# sha2017_rev1_0_0_1.net
KiCad netlist of a schematic drawn in Altium Designer
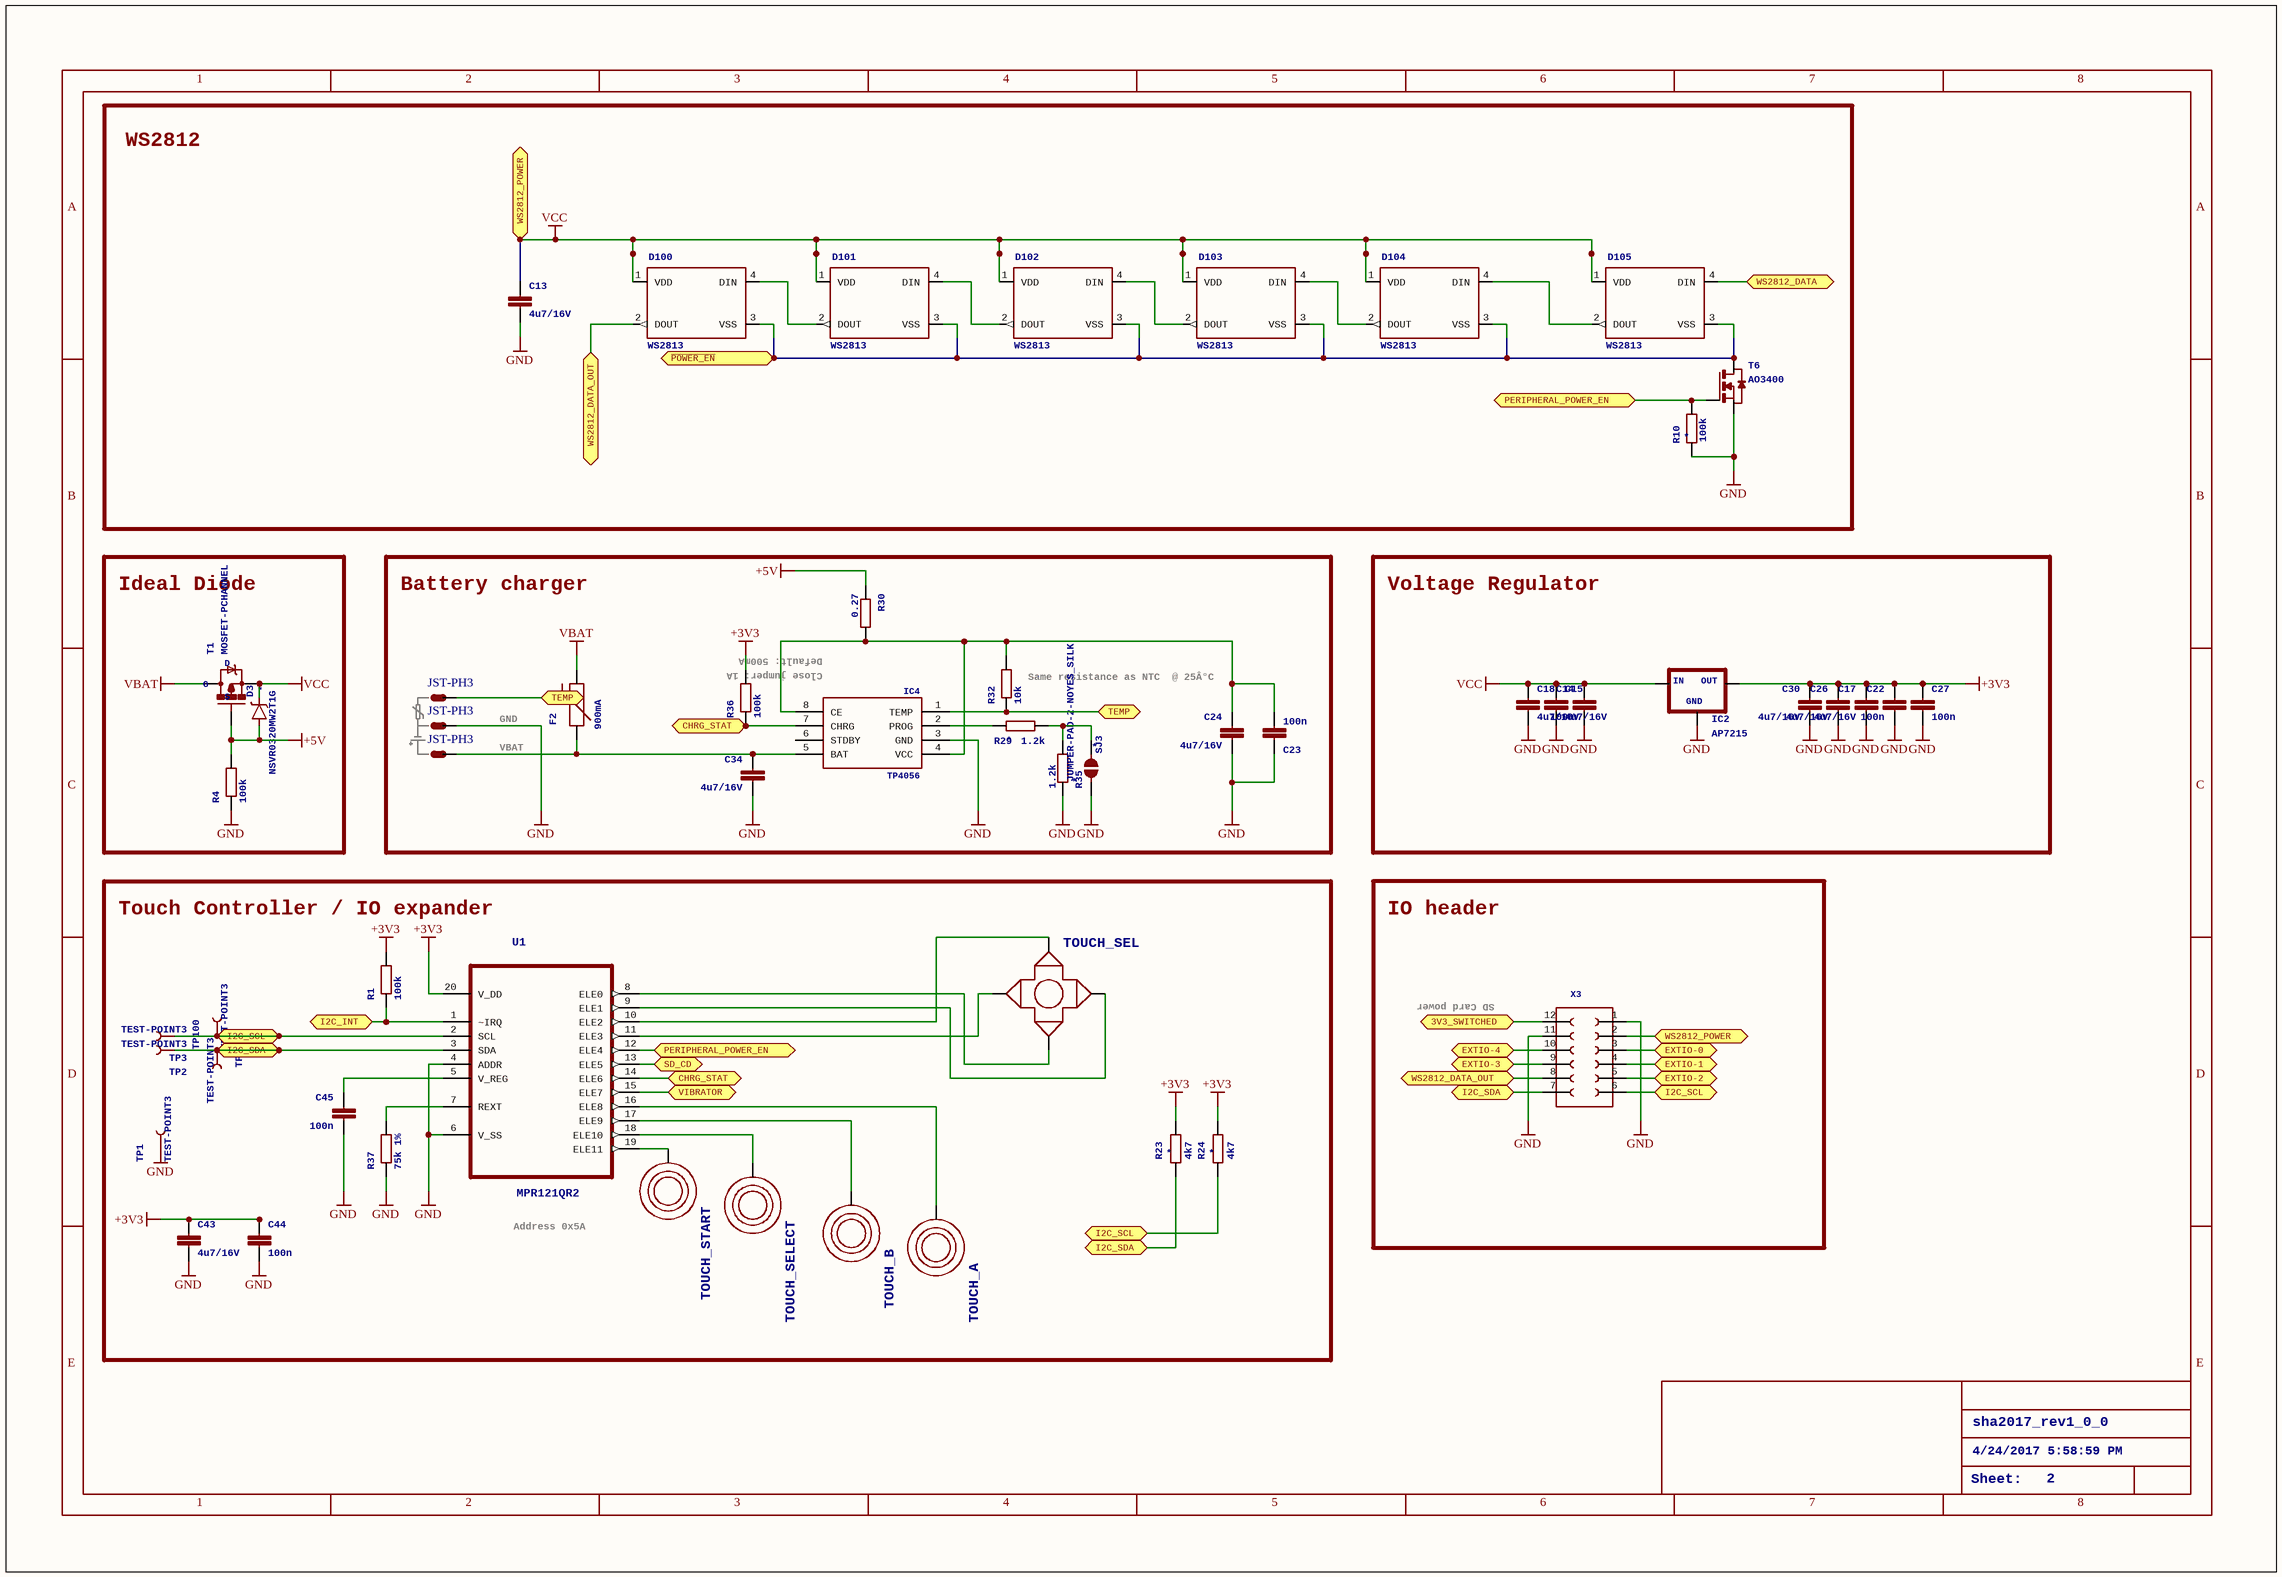
[diagram p0: sha2017_rev1_0_0_1.SchDoc]

(export (version "E")
  (design (tool "Eeschema 10.0.6"))
  (components
    (comp (ref "C13")
      (value "4u7/16V")
      (footprint "C0805")
      (description "CAPACITOR, European symbol")
      (libsource (lib "") (part "C-EUC0805_1"))
    )
    (comp (ref "C14") (value "100n") (footprint "C0603-DASHES") (libsource (lib "") (part "C0603-DASHES_1")))
    (comp (ref "C15")
      (value "4u7/16V")
      (footprint "C0805")
      (description "CAPACITOR, European symbol")
      (libsource (lib "") (part "C-EUC0805_1"))
    )
    (comp (ref "C17")
      (value "4u7/16V")
      (footprint "C0805")
      (description "CAPACITOR, European symbol")
      (libsource (lib "rcl") (part "C-EUC0805"))
    )
    (comp (ref "C18")
      (value "4u7/16V")
      (footprint "C0805")
      (description "CAPACITOR, European symbol")
      (libsource (lib "") (part "C-EUC0805_1"))
    )
    (comp (ref "C22") (value "100n") (footprint "C0603-DASHES") (libsource (lib "") (part "C0603-DASHES_1")))
    (comp (ref "C23")
      (value "100n")
      (footprint "C0603-DASHES")
      (libsource (lib "sha2017_rev0_1_0_dev") (part "C0603-DASHES"))
    )
    (comp (ref "C24")
      (value "4u7/16V")
      (footprint "C0805")
      (description "CAPACITOR, European symbol")
      (libsource (lib "rcl") (part "C-EUC0805"))
    )
    (comp (ref "C26")
      (value "4u7/16V")
      (footprint "C0805")
      (description "CAPACITOR, European symbol")
      (libsource (lib "rcl") (part "C-EUC0805"))
    )
    (comp (ref "C27") (value "100n") (footprint "C0603-DASHES") (libsource (lib "") (part "C0603-DASHES_2")))
    (comp (ref "C30")
      (value "4u7/16V")
      (footprint "C0805")
      (description "CAPACITOR, European symbol")
      (libsource (lib "rcl") (part "C-EUC0805"))
    )
    (comp (ref "C34")
      (value "4u7/16V")
      (footprint "C0805")
      (description "CAPACITOR, European symbol")
      (libsource (lib "rcl") (part "C-EUC0805"))
    )
    (comp (ref "C43")
      (value "4u7/16V")
      (footprint "C0805")
      (description "CAPACITOR, European symbol")
      (libsource (lib "") (part "C-EUC0805_1"))
    )
    (comp (ref "C44") (value "100n") (footprint "C0603-DASHES") (libsource (lib "") (part "C0603-DASHES_2")))
    (comp (ref "C45") (value "100n") (footprint "C0603-DASHES") (libsource (lib "") (part "C0603-DASHES_1")))
    (comp (ref "D3")
      (value "NSVR0320MW2T1G")
      (footprint "SOD-323")
      (description "23V, 1A Schottky diode, SOD-323 package")
      (fields (field (name "NAME") "*"))
      (libsource (lib "SparkFun-DiscreteSemi") (part "BAT20JFILM"))
    )
    (comp (ref "D100")
      (value "WS2813")
      (footprint "WS2812B")
      (libsource (lib "SparkFun-LED") (part "WS2812B"))
    )
    (comp (ref "D101")
      (value "WS2813")
      (footprint "WS2812B")
      (libsource (lib "SparkFun-LED") (part "WS2812B"))
    )
    (comp (ref "D102")
      (value "WS2813")
      (footprint "WS2812B")
      (libsource (lib "SparkFun-LED") (part "WS2812B"))
    )
    (comp (ref "D103")
      (value "WS2813")
      (footprint "WS2812B")
      (libsource (lib "SparkFun-LED") (part "WS2812B"))
    )
    (comp (ref "D104")
      (value "WS2813")
      (footprint "WS2812B")
      (libsource (lib "SparkFun-LED") (part "WS2812B"))
    )
    (comp (ref "D105")
      (value "WS2813")
      (footprint "WS2812B")
      (libsource (lib "SparkFun-LED") (part "WS2812B"))
    )
    (comp (ref "F2")
      (value "900mA")
      (footprint "PTC-1206")
      (description "Resettable Fuse PTCResettable Fuse. Spark Fun Electronics SKU : COM-08357")
      (libsource (lib "SparkFun-PowerIC") (part "PTCSMD"))
    )
    (comp (ref "IC2")
      (value "AP7215")
      (footprint "SOT89")
      (fields (field (name "GND") "GND") (field (name "IN") "IN") (field (name "OUT") "OUT"))
      (libsource (lib "badge") (part "AP7215"))
    )
    (comp (ref "IC4") (value "TP4056") (footprint "SOP-8") (libsource (lib "TP4056") (part "TP4056")))
    (comp (ref "R1")
      (value "100k")
      (footprint "R0603-DASHES")
      (libsource (lib "sha2017_rev0_1_0_dev") (part "R0603-DASHES"))
    )
    (comp (ref "R4")
      (value "100k")
      (footprint "R0603-DASHES")
      (libsource (lib "sha2017_rev0_1_0_dev") (part "R0603-DASHES"))
    )
    (comp (ref "R10")
      (value "100k")
      (footprint "R0603-DASHES")
      (fields (field (name "NAME") "*"))
      (libsource (lib "00ralf") (part "R0603-DASHES"))
    )
    (comp (ref "R23")
      (value "4k7")
      (footprint "R0603-DASHES")
      (fields (field (name "NAME") "*"))
      (libsource (lib "sha2017_rev0_1_0_dev") (part "R0603-DASHES"))
    )
    (comp (ref "R24")
      (value "4k7")
      (footprint "R0603-DASHES")
      (fields (field (name "NAME") "*"))
      (libsource (lib "sha2017_rev0_1_0_dev") (part "R0603-DASHES"))
    )
    (comp (ref "R29")
      (value "1.2k")
      (footprint "R0603-DASHES")
      (fields (field (name "NAME") "*"))
      (libsource (lib "sha2017_rev0_1_0_dev") (part "R0603-DASHES"))
    )
    (comp (ref "R30")
      (value "0.27")
      (footprint "R0603-DASHES")
      (libsource (lib "sha2017_rev0_1_0_dev") (part "R0603-DASHES"))
    )
    (comp (ref "R32")
      (value "10k")
      (footprint "R0603-DASHES")
      (libsource (lib "sha2017_rev0_1_0_dev") (part "R0603-DASHES"))
    )
    (comp (ref "R35")
      (value "1.2k")
      (footprint "R0603-DASHES")
      (fields (field (name "NAME") "*"))
      (libsource (lib "sha2017_rev0_1_0_dev") (part "R0603-DASHES"))
    )
    (comp (ref "R36")
      (value "100k")
      (footprint "R0603-DASHES")
      (libsource (lib "sha2017_rev0_1_0_dev") (part "R0603-DASHES"))
    )
    (comp (ref "R37")
      (value "75k 1%")
      (footprint "R0603-DASHES")
      (libsource (lib "sha2017_rev0_1_0_dev") (part "R0603-DASHES"))
    )
    (comp (ref "SJ3")
      (value "JUMPER-PAD-2-NOYES_SILK")
      (footprint "PAD-JUMPER-2-NO_YES_SILK")
      (fields (field (name "NAME") "*"))
      (libsource (lib "SparkFun-Passives") (part "JUMPER-PAD-2-NOYES_SILK"))
    )
    (comp (ref "T1")
      (value "MOSFET-PCHANNEL")
      (footprint "SOT23-3")
      (fields (field (name "D") "D") (field (name "S") "S") (field (name "G") "G"))
      (libsource (lib "SparkFun-DiscreteSemi") (part "MOSFET-PCHANNEL"))
    )
    (comp (ref "T6")
      (value "AO3400")
      (footprint "SOT-23")
      (description "MOS FET")
      (libsource (lib "zetex") (part "NMOSSOT23"))
    )
    (comp (ref "TOUCH_A")
      (value "TOUCHROUND")
      (footprint "TOUCH_BUTTON")
      (libsource (lib "badge") (part "TOUCHROUND"))
    )
    (comp (ref "TOUCH_B")
      (value "TOUCHROUND")
      (footprint "TOUCH_BUTTON")
      (libsource (lib "badge") (part "TOUCHROUND"))
    )
    (comp (ref "TOUCH_SEL")
      (value "TOUCH_CROSS")
      (footprint "TOUCH_CROSS")
      (libsource (lib "badge") (part "TOUCH_CROSS"))
    )
    (comp (ref "TOUCH_SELECT")
      (value "TOUCHSELECT")
      (footprint "TOUCH_SELECT")
      (libsource (lib "badge") (part "TOUCHSELECT"))
    )
    (comp (ref "TOUCH_START")
      (value "TOUCHSELECT")
      (footprint "TOUCH_SELECT")
      (libsource (lib "badge") (part "TOUCHSELECT"))
    )
    (comp (ref "TP1")
      (value "TEST-POINT3")
      (footprint "PAD.03X.03")
      (description "Bare copper test points for troubleshooting or ICT")
      (libsource (lib "SparkFun-Passives") (part "TEST-POINT3"))
    )
    (comp (ref "TP2")
      (value "TEST-POINT3")
      (footprint "PAD.03X.03")
      (description "Bare copper test points for troubleshooting or ICT")
      (libsource (lib "SparkFun-Passives") (part "TEST-POINT3"))
    )
    (comp (ref "TP3")
      (value "TEST-POINT3")
      (footprint "PAD.03X.03")
      (description "Bare copper test points for troubleshooting or ICT")
      (libsource (lib "SparkFun-Passives") (part "TEST-POINT3"))
    )
    (comp (ref "TP100")
      (value "TEST-POINT3")
      (footprint "PAD.03X.03")
      (description "Bare copper test points for troubleshooting or ICT")
      (libsource (lib "SparkFun-Passives") (part "TEST-POINT3"))
    )
    (comp (ref "TP101")
      (value "TEST-POINT3")
      (footprint "PAD.03X.03")
      (description "Bare copper test points for troubleshooting or ICT")
      (libsource (lib "SparkFun-Passives") (part "TEST-POINT3"))
    )
    (comp (ref "U1")
      (value "MPR121QR2")
      (footprint "QFN40P300X300X60-20N")
      (description "Proximity Capacitive Touch Sensor Controller")
      (libsource (lib "Freescale_By_element14_Batch_1") (part "MPR121QR2"))
    )
    (comp (ref "X3")
      (value "610X12243021")
      (footprint "610X12243021")
      (libsource (lib "EAGLE-BOARD-TO-BOARD_CONNECTORS-rev16c") (part "610X12243021"))
    )
    (comp (ref "X4") (value "JST-PH3") (footprint "JST-PH3") (libsource (lib "badge") (part "JST-PH3")))
  )
  (nets
    (net (code "1") (name "+3V3") (class "Default")
      (node (ref "C17") (pin "1") (pinfunction "1_1") (pintype "passive"))
      (node (ref "C22") (pin "1") (pinfunction "1_1") (pintype "passive"))
      (node (ref "C26") (pin "1") (pinfunction "1_1") (pintype "passive"))
      (node (ref "C27") (pin "1") (pinfunction "1_1") (pintype "passive"))
      (node (ref "C30") (pin "1") (pinfunction "1_1") (pintype "passive"))
      (node (ref "C43") (pin "1") (pinfunction "1_1") (pintype "passive"))
      (node (ref "C44") (pin "1") (pinfunction "1_1") (pintype "passive"))
      (node (ref "IC2") (pin "3") (pinfunction "OUT_3") (pintype "passive"))
      (node (ref "R1") (pin "2") (pinfunction "2_2") (pintype "passive"))
      (node (ref "R23") (pin "1") (pinfunction "1_1") (pintype "passive"))
      (node (ref "R24") (pin "1") (pinfunction "1_1") (pintype "passive"))
      (node (ref "R36") (pin "2") (pinfunction "2_2") (pintype "passive"))
      (node (ref "U1") (pin "20") (pinfunction "V_DD_20") (pintype "power_in"))
    )
    (net (code "2") (name "+5V") (class "Default")
      (node (ref "D3") (pin "A") (pinfunction "A_A") (pintype "passive"))
      (node (ref "R30") (pin "1") (pinfunction "1_1") (pintype "passive"))
      (node (ref "R4") (pin "2") (pinfunction "2_2") (pintype "passive"))
      (node (ref "T1") (pin "1") (pinfunction "G_1") (pintype "passive"))
    )
    (net (code "3") (name "/3V3_SWITCHED") (class "Default")
      (node (ref "X3") (pin "12") (pinfunction "1_12") (pintype "passive"))
    )
    (net (code "4") (name "/CHRG_STAT") (class "Default")
      (node (ref "IC4") (pin "7") (pinfunction "CHRG_7") (pintype "passive"))
      (node (ref "R36") (pin "1") (pinfunction "1_1") (pintype "passive"))
      (node (ref "U1") (pin "14") (pinfunction "ELE6_14") (pintype "output"))
    )
    (net (code "5") (name "/EXTIO-0") (class "Default")
      (node (ref "X3") (pin "3") (pinfunction "10_3") (pintype "passive"))
    )
    (net (code "6") (name "/EXTIO-1") (class "Default")
      (node (ref "X3") (pin "4") (pinfunction "9_4") (pintype "passive"))
    )
    (net (code "7") (name "/EXTIO-2") (class "Default")
      (node (ref "X3") (pin "5") (pinfunction "8_5") (pintype "passive"))
    )
    (net (code "8") (name "/EXTIO-3") (class "Default")
      (node (ref "X3") (pin "9") (pinfunction "4_9") (pintype "passive"))
    )
    (net (code "9") (name "/EXTIO-4") (class "Default")
      (node (ref "X3") (pin "10") (pinfunction "3_10") (pintype "passive"))
    )
    (net (code "10") (name "/I2C_INT") (class "Default")
      (node (ref "R1") (pin "1") (pinfunction "1_1") (pintype "passive"))
      (node (ref "U1") (pin "1") (pinfunction "~IRQ_1") (pintype "passive"))
    )
    (net (code "11") (name "/I2C_SCL") (class "Default")
      (node (ref "R24") (pin "2") (pinfunction "2_2") (pintype "passive"))
      (node (ref "TP100") (pin "P$1") (pinfunction "1_P$1") (pintype "passive"))
      (node (ref "TP3") (pin "P$1") (pinfunction "1_P$1") (pintype "passive"))
      (node (ref "U1") (pin "2") (pinfunction "SCL_2") (pintype "passive"))
      (node (ref "X3") (pin "6") (pinfunction "7_6") (pintype "passive"))
    )
    (net (code "12") (name "/I2C_SDA") (class "Default")
      (node (ref "R23") (pin "2") (pinfunction "2_2") (pintype "passive"))
      (node (ref "TP101") (pin "P$1") (pinfunction "1_P$1") (pintype "passive"))
      (node (ref "TP2") (pin "P$1") (pinfunction "1_P$1") (pintype "passive"))
      (node (ref "U1") (pin "3") (pinfunction "SDA_3") (pintype "passive"))
      (node (ref "X3") (pin "7") (pinfunction "6_7") (pintype "passive"))
    )
    (net (code "13") (name "/PERIPHERAL_POWER_EN") (class "Default")
      (node (ref "R10") (pin "1") (pinfunction "1_1") (pintype "passive"))
      (node (ref "T6") (pin "3") (pinfunction "G_3") (pintype "passive"))
      (node (ref "U1") (pin "12") (pinfunction "ELE4_12") (pintype "output"))
    )
    (net (code "14") (name "/SD_CD") (class "Default")
      (node (ref "U1") (pin "13") (pinfunction "ELE5_13") (pintype "output"))
    )
    (net (code "15") (name "/TEMP") (class "Default")
      (node (ref "IC4") (pin "1") (pinfunction "TEMP_1") (pintype "passive"))
      (node (ref "R32") (pin "1") (pinfunction "1_1") (pintype "passive"))
      (node (ref "X4") (pin "1") (pinfunction "1_1") (pintype "passive"))
    )
    (net (code "16") (name "/VIBRATOR") (class "Default")
      (node (ref "U1") (pin "15") (pinfunction "ELE7_15") (pintype "output"))
    )
    (net (code "17") (name "/WS2812_DATA") (class "Default")
      (node (ref "D105") (pin "4") (pinfunction "DIN_4") (pintype "passive"))
    )
    (net (code "18") (name "/WS2812_DATA_OUT") (class "Default")
      (node (ref "D100") (pin "2") (pinfunction "DOUT_2") (pintype "output"))
      (node (ref "X3") (pin "8") (pinfunction "5_8") (pintype "passive"))
    )
    (net (code "19") (name "/~{POWER_EN}") (class "Default")
      (node (ref "D100") (pin "3") (pinfunction "VSS_3") (pintype "power_in"))
      (node (ref "D101") (pin "3") (pinfunction "VSS_3") (pintype "power_in"))
      (node (ref "D102") (pin "3") (pinfunction "VSS_3") (pintype "power_in"))
      (node (ref "D103") (pin "3") (pinfunction "VSS_3") (pintype "power_in"))
      (node (ref "D104") (pin "3") (pinfunction "VSS_3") (pintype "power_in"))
      (node (ref "D105") (pin "3") (pinfunction "VSS_3") (pintype "power_in"))
      (node (ref "T6") (pin "1") (pinfunction "D_1") (pintype "passive"))
    )
    (net (code "20") (name "GND") (class "Default")
      (node (ref "C13") (pin "2") (pinfunction "2_2") (pintype "passive"))
      (node (ref "C14") (pin "2") (pinfunction "2_2") (pintype "passive"))
      (node (ref "C15") (pin "2") (pinfunction "2_2") (pintype "passive"))
      (node (ref "C17") (pin "2") (pinfunction "2_2") (pintype "passive"))
      (node (ref "C18") (pin "2") (pinfunction "2_2") (pintype "passive"))
      (node (ref "C22") (pin "2") (pinfunction "2_2") (pintype "passive"))
      (node (ref "C23") (pin "1") (pinfunction "1_1") (pintype "passive"))
      (node (ref "C24") (pin "2") (pinfunction "2_2") (pintype "passive"))
      (node (ref "C26") (pin "2") (pinfunction "2_2") (pintype "passive"))
      (node (ref "C27") (pin "2") (pinfunction "2_2") (pintype "passive"))
      (node (ref "C30") (pin "2") (pinfunction "2_2") (pintype "passive"))
      (node (ref "C34") (pin "2") (pinfunction "2_2") (pintype "passive"))
      (node (ref "C43") (pin "2") (pinfunction "2_2") (pintype "passive"))
      (node (ref "C44") (pin "2") (pinfunction "2_2") (pintype "passive"))
      (node (ref "C45") (pin "2") (pinfunction "2_2") (pintype "passive"))
      (node (ref "IC2") (pin "1") (pinfunction "GND_1") (pintype "passive"))
      (node (ref "IC4") (pin "3") (pinfunction "GND_3") (pintype "passive"))
      (node (ref "R10") (pin "2") (pinfunction "2_2") (pintype "passive"))
      (node (ref "R35") (pin "2") (pinfunction "2_2") (pintype "passive"))
      (node (ref "R37") (pin "1") (pinfunction "1_1") (pintype "passive"))
      (node (ref "R4") (pin "1") (pinfunction "1_1") (pintype "passive"))
      (node (ref "SJ3") (pin "1") (pinfunction "1_1") (pintype "passive"))
      (node (ref "T6") (pin "2") (pinfunction "S_2") (pintype "passive"))
      (node (ref "TP1") (pin "P$1") (pinfunction "1_P$1") (pintype "passive"))
      (node (ref "U1") (pin "4") (pinfunction "ADDR_4") (pintype "passive"))
      (node (ref "U1") (pin "6") (pinfunction "V_SS_6") (pintype "power_in"))
      (node (ref "X3") (pin "1") (pinfunction "12_1") (pintype "passive"))
      (node (ref "X3") (pin "11") (pinfunction "2_11") (pintype "passive"))
      (node (ref "X4") (pin "2") (pinfunction "1_2") (pintype "passive"))
    )
    (net (code "21") (name "Net-(D100-DIN)") (class "Default")
      (node (ref "D100") (pin "4") (pinfunction "DIN_4") (pintype "passive"))
      (node (ref "D101") (pin "2") (pinfunction "DOUT_2") (pintype "output"))
    )
    (net (code "22") (name "Net-(D101-DIN)") (class "Default")
      (node (ref "D101") (pin "4") (pinfunction "DIN_4") (pintype "passive"))
      (node (ref "D102") (pin "2") (pinfunction "DOUT_2") (pintype "output"))
    )
    (net (code "23") (name "Net-(D102-DIN)") (class "Default")
      (node (ref "D102") (pin "4") (pinfunction "DIN_4") (pintype "passive"))
      (node (ref "D103") (pin "2") (pinfunction "DOUT_2") (pintype "output"))
    )
    (net (code "24") (name "Net-(D103-DIN)") (class "Default")
      (node (ref "D103") (pin "4") (pinfunction "DIN_4") (pintype "passive"))
      (node (ref "D104") (pin "2") (pinfunction "DOUT_2") (pintype "output"))
    )
    (net (code "25") (name "Net-(D104-DIN)") (class "Default")
      (node (ref "D104") (pin "4") (pinfunction "DIN_4") (pintype "passive"))
      (node (ref "D105") (pin "2") (pinfunction "DOUT_2") (pintype "output"))
    )
    (net (code "26") (name "Net-(IC4-BAT)") (class "Default")
      (node (ref "C34") (pin "1") (pinfunction "1_1") (pintype "passive"))
      (node (ref "F2") (pin "1") (pinfunction "1_1") (pintype "passive"))
      (node (ref "IC4") (pin "5") (pinfunction "BAT_5") (pintype "passive"))
      (node (ref "X4") (pin "3") (pinfunction "1_3") (pintype "passive"))
    )
    (net (code "27") (name "Net-(IC4-CE)") (class "Default")
      (node (ref "C23") (pin "2") (pinfunction "2_2") (pintype "passive"))
      (node (ref "C24") (pin "1") (pinfunction "1_1") (pintype "passive"))
      (node (ref "IC4") (pin "4") (pinfunction "VCC_4") (pintype "passive"))
      (node (ref "IC4") (pin "8") (pinfunction "CE_8") (pintype "passive"))
      (node (ref "R30") (pin "2") (pinfunction "2_2") (pintype "passive"))
      (node (ref "R32") (pin "2") (pinfunction "2_2") (pintype "passive"))
    )
    (net (code "28") (name "Net-(IC4-PROG)") (class "Default")
      (node (ref "IC4") (pin "2") (pinfunction "PROG_2") (pintype "passive"))
      (node (ref "R29") (pin "1") (pinfunction "1_1") (pintype "passive"))
    )
    (net (code "29") (name "Net-(R29-Pad2)") (class "Default")
      (node (ref "R29") (pin "2") (pinfunction "2_2") (pintype "passive"))
      (node (ref "R35") (pin "1") (pinfunction "1_1") (pintype "passive"))
      (node (ref "SJ3") (pin "2") (pinfunction "2_2") (pintype "passive"))
    )
    (net (code "30") (name "Net-(TOUCH_SEL-DOWN)") (class "Default")
      (node (ref "TOUCH_SEL") (pin "D") (pinfunction "DOWN_D") (pintype "passive"))
      (node (ref "U1") (pin "8") (pinfunction "ELE0_8") (pintype "output"))
    )
    (net (code "31") (name "Net-(TOUCH_SEL-LEFT)") (class "Default")
      (node (ref "TOUCH_SEL") (pin "L") (pinfunction "LEFT_L") (pintype "passive"))
      (node (ref "U1") (pin "11") (pinfunction "ELE3_11") (pintype "output"))
    )
    (net (code "32") (name "Net-(TOUCH_SEL-RIGHT)") (class "Default")
      (node (ref "TOUCH_SEL") (pin "R") (pinfunction "RIGHT_R") (pintype "passive"))
      (node (ref "U1") (pin "9") (pinfunction "ELE1_9") (pintype "output"))
    )
    (net (code "33") (name "Net-(U1-ELE2)") (class "Default")
      (node (ref "TOUCH_SEL") (pin "UP") (pinfunction "UP_UP") (pintype "passive"))
      (node (ref "U1") (pin "10") (pinfunction "ELE2_10") (pintype "output"))
    )
    (net (code "34") (name "Net-(U1-ELE8)") (class "Default")
      (node (ref "TOUCH_A") (pin "P$1") (pinfunction "P$1_P$1") (pintype "passive"))
      (node (ref "U1") (pin "16") (pinfunction "ELE8_16") (pintype "output"))
    )
    (net (code "35") (name "Net-(U1-ELE9)") (class "Default")
      (node (ref "TOUCH_B") (pin "P$1") (pinfunction "P$1_P$1") (pintype "passive"))
      (node (ref "U1") (pin "17") (pinfunction "ELE9_17") (pintype "output"))
    )
    (net (code "36") (name "Net-(U1-ELE10)") (class "Default")
      (node (ref "TOUCH_SELECT") (pin "P$1") (pinfunction "P$1_P$1") (pintype "passive"))
      (node (ref "U1") (pin "18") (pinfunction "ELE10_18") (pintype "output"))
    )
    (net (code "37") (name "Net-(U1-ELE11)") (class "Default")
      (node (ref "TOUCH_START") (pin "P$1") (pinfunction "P$1_P$1") (pintype "passive"))
      (node (ref "U1") (pin "19") (pinfunction "ELE11_19") (pintype "output"))
    )
    (net (code "38") (name "Net-(U1-REXT)") (class "Default")
      (node (ref "R37") (pin "2") (pinfunction "2_2") (pintype "passive"))
      (node (ref "U1") (pin "7") (pinfunction "REXT_7") (pintype "passive"))
    )
    (net (code "39") (name "Net-(U1-V_REG)") (class "Default")
      (node (ref "C45") (pin "1") (pinfunction "1_1") (pintype "passive"))
      (node (ref "U1") (pin "5") (pinfunction "V_REG_5") (pintype "passive"))
    )
    (net (code "40") (name "VBAT") (class "Default")
      (node (ref "F2") (pin "2") (pinfunction "2_2") (pintype "passive"))
      (node (ref "T1") (pin "3") (pinfunction "D_3") (pintype "passive"))
    )
    (net (code "41") (name "VCC") (class "Default")
      (node (ref "C13") (pin "1") (pinfunction "1_1") (pintype "passive"))
      (node (ref "C14") (pin "1") (pinfunction "1_1") (pintype "passive"))
      (node (ref "C15") (pin "1") (pinfunction "1_1") (pintype "passive"))
      (node (ref "C18") (pin "1") (pinfunction "1_1") (pintype "passive"))
      (node (ref "D100") (pin "1") (pinfunction "VDD_1") (pintype "power_in"))
      (node (ref "D101") (pin "1") (pinfunction "VDD_1") (pintype "power_in"))
      (node (ref "D102") (pin "1") (pinfunction "VDD_1") (pintype "power_in"))
      (node (ref "D103") (pin "1") (pinfunction "VDD_1") (pintype "power_in"))
      (node (ref "D104") (pin "1") (pinfunction "VDD_1") (pintype "power_in"))
      (node (ref "D105") (pin "1") (pinfunction "VDD_1") (pintype "power_in"))
      (node (ref "D3") (pin "C") (pinfunction "C_C") (pintype "passive"))
      (node (ref "IC2") (pin "2_2@") (pinfunction "IN_2_2@") (pintype "passive"))
      (node (ref "T1") (pin "2") (pinfunction "S_2") (pintype "passive"))
      (node (ref "X3") (pin "2") (pinfunction "11_2") (pintype "passive"))
    )
    (net (code "42") (name "unconnected-(IC4-STDBY-Pad6)") (class "Default")
      (node (ref "IC4") (pin "6") (pinfunction "STDBY_6") (pintype "passive"))
    )
  )
)
